# untitled.net
KiCad netlist of a schematic drawn in EAGLE
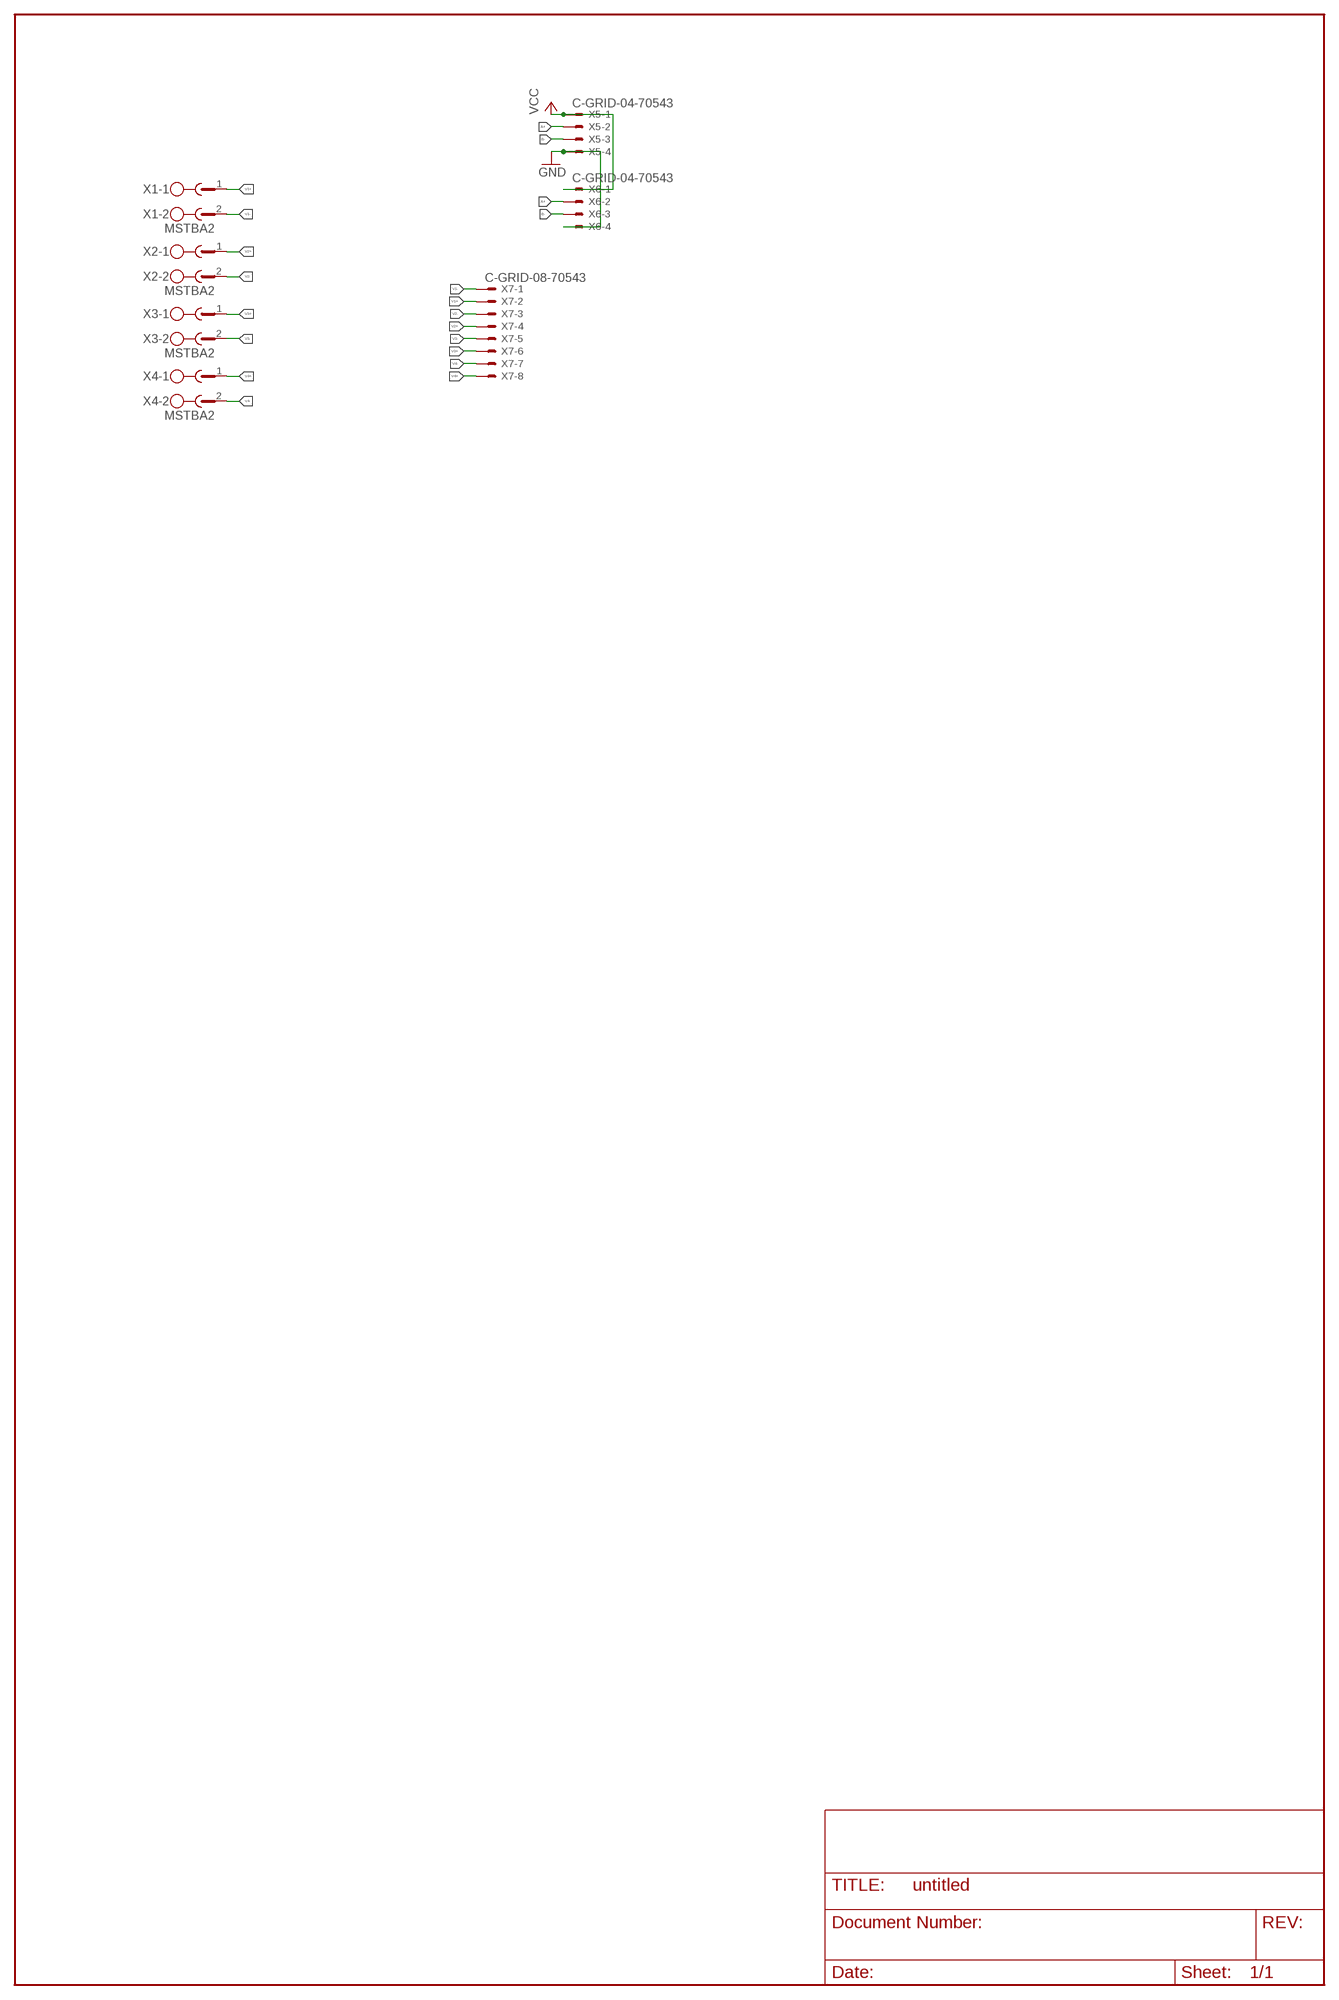
[diagram p0: schematic, sheet 1]

(export (version "E")
  (design (tool "Eeschema 10.0.6"))
  (components
    (comp (ref "X1")
      (value "MSTBA2")
      (footprint "eagle-import:MSTBA2")
      (fields (field (name "MF") "FARNELL") (field (name "MPN") "1757242"))
      (libsource (lib "eagle-import") (part "MSTBA2"))
    )
    (comp (ref "X2")
      (value "MSTBA2")
      (footprint "eagle-import:MSTBA2")
      (fields (field (name "MF") "FARNELL") (field (name "MPN") "1757242"))
      (libsource (lib "eagle-import") (part "MSTBA2"))
    )
    (comp (ref "X3")
      (value "MSTBA2")
      (footprint "eagle-import:MSTBA2")
      (fields (field (name "MF") "FARNELL") (field (name "MPN") "1757242"))
      (libsource (lib "eagle-import") (part "MSTBA2"))
    )
    (comp (ref "X4")
      (value "MSTBA2")
      (footprint "eagle-import:MSTBA2")
      (fields (field (name "MF") "FARNELL") (field (name "MPN") "1757242"))
      (libsource (lib "eagle-import") (part "MSTBA2"))
    )
    (comp (ref "X5")
      (value "C-GRID-04-70543")
      (footprint "eagle-import:70543-04")
      (fields (field (name "MF") "MOLEX"))
      (libsource (lib "eagle-import") (part "C-GRID-04-70543"))
    )
    (comp (ref "X6")
      (value "C-GRID-04-70543")
      (footprint "eagle-import:70543-04")
      (fields (field (name "MF") "MOLEX"))
      (libsource (lib "eagle-import") (part "C-GRID-04-70543"))
    )
    (comp (ref "X7")
      (value "C-GRID-08-70543")
      (footprint "eagle-import:70543-08")
      (fields (field (name "MF") "MOLEX"))
      (libsource (lib "eagle-import") (part "C-GRID-08-70543"))
    )
  )
  (nets
    (net (code "1") (name "A+") (class "Default")
      (node (ref "X5") (pin "2") (pinfunction "S_2") (pintype "passive"))
      (node (ref "X6") (pin "2") (pinfunction "S_2") (pintype "passive"))
    )
    (net (code "2") (name "B-") (class "Default")
      (node (ref "X5") (pin "3") (pinfunction "S_3") (pintype "passive"))
      (node (ref "X6") (pin "3") (pinfunction "S_3") (pintype "passive"))
    )
    (net (code "3") (name "GND") (class "Default")
      (node (ref "X5") (pin "4") (pinfunction "S_4") (pintype "passive"))
      (node (ref "X6") (pin "4") (pinfunction "S_4") (pintype "passive"))
    )
    (net (code "4") (name "V1+") (class "Default")
      (node (ref "X1") (pin "1") (pinfunction "1_1") (pintype "passive"))
      (node (ref "X7") (pin "2") (pinfunction "S_2") (pintype "passive"))
    )
    (net (code "5") (name "V1-") (class "Default")
      (node (ref "X1") (pin "2") (pinfunction "1_2") (pintype "passive"))
      (node (ref "X7") (pin "1") (pinfunction "S_1") (pintype "passive"))
    )
    (net (code "6") (name "V2+") (class "Default")
      (node (ref "X2") (pin "1") (pinfunction "1_1") (pintype "passive"))
      (node (ref "X7") (pin "4") (pinfunction "S_4") (pintype "passive"))
    )
    (net (code "7") (name "V2-") (class "Default")
      (node (ref "X2") (pin "2") (pinfunction "1_2") (pintype "passive"))
      (node (ref "X7") (pin "3") (pinfunction "S_3") (pintype "passive"))
    )
    (net (code "8") (name "V3+") (class "Default")
      (node (ref "X3") (pin "1") (pinfunction "1_1") (pintype "passive"))
      (node (ref "X7") (pin "6") (pinfunction "S_6") (pintype "passive"))
    )
    (net (code "9") (name "V3-") (class "Default")
      (node (ref "X3") (pin "2") (pinfunction "1_2") (pintype "passive"))
      (node (ref "X7") (pin "5") (pinfunction "S_5") (pintype "passive"))
    )
    (net (code "10") (name "V4+") (class "Default")
      (node (ref "X4") (pin "1") (pinfunction "1_1") (pintype "passive"))
      (node (ref "X7") (pin "8") (pinfunction "S_8") (pintype "passive"))
    )
    (net (code "11") (name "V4-") (class "Default")
      (node (ref "X4") (pin "2") (pinfunction "1_2") (pintype "passive"))
      (node (ref "X7") (pin "7") (pinfunction "S_7") (pintype "passive"))
    )
    (net (code "12") (name "VCC") (class "Default")
      (node (ref "X5") (pin "1") (pinfunction "S_1") (pintype "passive"))
      (node (ref "X6") (pin "1") (pinfunction "S_1") (pintype "passive"))
    )
  )
)
